# MOS_Switch.net
KiCad netlist of a schematic drawn in Altium Designer
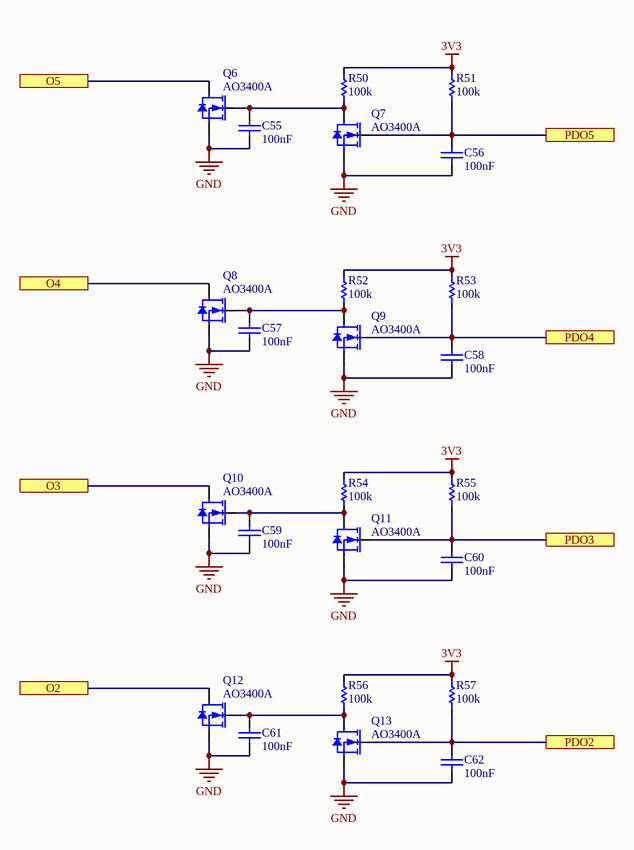
[diagram p0: MOS Switch.SchDoc]

(export (version "E")
  (design (tool "Eeschema 10.0.6"))
  (components
    (comp (ref "C55")
      (value "100nF")
      (footprint "CAP_CHIP_0603")
      (description "0603 Multilayer Ceramic Capacitors MLCC")
      (fields (field (name "PARTNUMBER") "CC0603KRX7R9BB104") (field (name "TOLERANCE") "10%"))
      (libsource (lib "Sainsbury Wellcome Centre") (part "Cap"))
    )
    (comp (ref "C56")
      (value "100nF")
      (footprint "CAP_CHIP_0603")
      (description "0603 Multilayer Ceramic Capacitors MLCC")
      (fields (field (name "PARTNUMBER") "CC0603KRX7R9BB104") (field (name "TOLERANCE") "10%"))
      (libsource (lib "Sainsbury Wellcome Centre") (part "Cap"))
    )
    (comp (ref "C57")
      (value "100nF")
      (footprint "CAP_CHIP_0603")
      (description "0603 Multilayer Ceramic Capacitors MLCC")
      (fields (field (name "PARTNUMBER") "CC0603KRX7R9BB104") (field (name "TOLERANCE") "10%"))
      (libsource (lib "Sainsbury Wellcome Centre") (part "Cap"))
    )
    (comp (ref "C58")
      (value "100nF")
      (footprint "CAP_CHIP_0603")
      (description "0603 Multilayer Ceramic Capacitors MLCC")
      (fields (field (name "PARTNUMBER") "CC0603KRX7R9BB104") (field (name "TOLERANCE") "10%"))
      (libsource (lib "Sainsbury Wellcome Centre") (part "Cap"))
    )
    (comp (ref "C59")
      (value "100nF")
      (footprint "CAP_CHIP_0603")
      (description "0603 Multilayer Ceramic Capacitors MLCC")
      (fields (field (name "PARTNUMBER") "CC0603KRX7R9BB104") (field (name "TOLERANCE") "10%"))
      (libsource (lib "Sainsbury Wellcome Centre") (part "Cap"))
    )
    (comp (ref "C60")
      (value "100nF")
      (footprint "CAP_CHIP_0603")
      (description "0603 Multilayer Ceramic Capacitors MLCC")
      (fields (field (name "PARTNUMBER") "CC0603KRX7R9BB104") (field (name "TOLERANCE") "10%"))
      (libsource (lib "Sainsbury Wellcome Centre") (part "Cap"))
    )
    (comp (ref "C61")
      (value "100nF")
      (footprint "CAP_CHIP_0603")
      (description "0603 Multilayer Ceramic Capacitors MLCC")
      (fields (field (name "PARTNUMBER") "CC0603KRX7R9BB104") (field (name "TOLERANCE") "10%"))
      (libsource (lib "Sainsbury Wellcome Centre") (part "Cap"))
    )
    (comp (ref "C62")
      (value "100nF")
      (footprint "CAP_CHIP_0603")
      (description "0603 Multilayer Ceramic Capacitors MLCC")
      (fields (field (name "PARTNUMBER") "CC0603KRX7R9BB104") (field (name "TOLERANCE") "10%"))
      (libsource (lib "Sainsbury Wellcome Centre") (part "Cap"))
    )
    (comp (ref "Q6")
      (value "AO3400A")
      (footprint "SOT23")
      (description "30V 5.7A 26.5mΩ@10V,5.7A 1.4W 1.5V@250uA 1 NChannel SOT-23-3L MOSFETs")
      (fields (field (name "PARTNUMBER") "AO3400A"))
      (libsource (lib "Sainsbury Wellcome Centre") (part "NMOS"))
    )
    (comp (ref "Q7")
      (value "AO3400A")
      (footprint "SOT23")
      (description "30V 5.7A 26.5mΩ@10V,5.7A 1.4W 1.5V@250uA 1 NChannel SOT-23-3L MOSFETs")
      (fields (field (name "PARTNUMBER") "AO3400A"))
      (libsource (lib "Sainsbury Wellcome Centre") (part "NMOS"))
    )
    (comp (ref "Q8")
      (value "AO3400A")
      (footprint "SOT23")
      (description "30V 5.7A 26.5mΩ@10V,5.7A 1.4W 1.5V@250uA 1 NChannel SOT-23-3L MOSFETs")
      (fields (field (name "PARTNUMBER") "AO3400A"))
      (libsource (lib "Sainsbury Wellcome Centre") (part "NMOS"))
    )
    (comp (ref "Q9")
      (value "AO3400A")
      (footprint "SOT23")
      (description "30V 5.7A 26.5mΩ@10V,5.7A 1.4W 1.5V@250uA 1 NChannel SOT-23-3L MOSFETs")
      (fields (field (name "PARTNUMBER") "AO3400A"))
      (libsource (lib "Sainsbury Wellcome Centre") (part "NMOS"))
    )
    (comp (ref "Q10")
      (value "AO3400A")
      (footprint "SOT23")
      (description "30V 5.7A 26.5mΩ@10V,5.7A 1.4W 1.5V@250uA 1 NChannel SOT-23-3L MOSFETs")
      (fields (field (name "PARTNUMBER") "AO3400A"))
      (libsource (lib "Sainsbury Wellcome Centre") (part "NMOS"))
    )
    (comp (ref "Q11")
      (value "AO3400A")
      (footprint "SOT23")
      (description "30V 5.7A 26.5mΩ@10V,5.7A 1.4W 1.5V@250uA 1 NChannel SOT-23-3L MOSFETs")
      (fields (field (name "PARTNUMBER") "AO3400A"))
      (libsource (lib "Sainsbury Wellcome Centre") (part "NMOS"))
    )
    (comp (ref "Q12")
      (value "AO3400A")
      (footprint "SOT23")
      (description "30V 5.7A 26.5mΩ@10V,5.7A 1.4W 1.5V@250uA 1 NChannel SOT-23-3L MOSFETs")
      (fields (field (name "PARTNUMBER") "AO3400A"))
      (libsource (lib "Sainsbury Wellcome Centre") (part "NMOS"))
    )
    (comp (ref "Q13")
      (value "AO3400A")
      (footprint "SOT23")
      (description "30V 5.7A 26.5mΩ@10V,5.7A 1.4W 1.5V@250uA 1 NChannel SOT-23-3L MOSFETs")
      (fields (field (name "PARTNUMBER") "AO3400A"))
      (libsource (lib "Sainsbury Wellcome Centre") (part "NMOS"))
    )
    (comp (ref "R50")
      (value "100k")
      (footprint "RES_CHIP_0603")
      (description "100mW Thick Film Resistors 75V ±100ppm/℃ ±1% 0603 Chip Resistor")
      (fields (field (name "PARTNUMBER") "0603WAF1003T5E") (field (name "TOLERANCE") "1%"))
      (libsource (lib "Sainsbury Wellcome Centre") (part "Res"))
    )
    (comp (ref "R51")
      (value "100k")
      (footprint "RES_CHIP_0603")
      (description "100mW Thick Film Resistors 75V ±100ppm/℃ ±1% 0603 Chip Resistor")
      (fields (field (name "PARTNUMBER") "0603WAF1003T5E") (field (name "TOLERANCE") "1%"))
      (libsource (lib "Sainsbury Wellcome Centre") (part "Res"))
    )
    (comp (ref "R52")
      (value "100k")
      (footprint "RES_CHIP_0603")
      (description "100mW Thick Film Resistors 75V ±100ppm/℃ ±1% 0603 Chip Resistor")
      (fields (field (name "PARTNUMBER") "0603WAF1003T5E") (field (name "TOLERANCE") "1%"))
      (libsource (lib "Sainsbury Wellcome Centre") (part "Res"))
    )
    (comp (ref "R53")
      (value "100k")
      (footprint "RES_CHIP_0603")
      (description "100mW Thick Film Resistors 75V ±100ppm/℃ ±1% 0603 Chip Resistor")
      (fields (field (name "PARTNUMBER") "0603WAF1003T5E") (field (name "TOLERANCE") "1%"))
      (libsource (lib "Sainsbury Wellcome Centre") (part "Res"))
    )
    (comp (ref "R54")
      (value "100k")
      (footprint "RES_CHIP_0603")
      (description "100mW Thick Film Resistors 75V ±100ppm/℃ ±1% 0603 Chip Resistor")
      (fields (field (name "PARTNUMBER") "0603WAF1003T5E") (field (name "TOLERANCE") "1%"))
      (libsource (lib "Sainsbury Wellcome Centre") (part "Res"))
    )
    (comp (ref "R55")
      (value "100k")
      (footprint "RES_CHIP_0603")
      (description "100mW Thick Film Resistors 75V ±100ppm/℃ ±1% 0603 Chip Resistor")
      (fields (field (name "PARTNUMBER") "0603WAF1003T5E") (field (name "TOLERANCE") "1%"))
      (libsource (lib "Sainsbury Wellcome Centre") (part "Res"))
    )
    (comp (ref "R56")
      (value "100k")
      (footprint "RES_CHIP_0603")
      (description "100mW Thick Film Resistors 75V ±100ppm/℃ ±1% 0603 Chip Resistor")
      (fields (field (name "PARTNUMBER") "0603WAF1003T5E") (field (name "TOLERANCE") "1%"))
      (libsource (lib "Sainsbury Wellcome Centre") (part "Res"))
    )
    (comp (ref "R57")
      (value "100k")
      (footprint "RES_CHIP_0603")
      (description "100mW Thick Film Resistors 75V ±100ppm/℃ ±1% 0603 Chip Resistor")
      (fields (field (name "PARTNUMBER") "0603WAF1003T5E") (field (name "TOLERANCE") "1%"))
      (libsource (lib "Sainsbury Wellcome Centre") (part "Res"))
    )
  )
  (nets
    (net (code "1") (name "/O2") (class "Default")
      (node (ref "Q12") (pin "3") (pinfunction "D_3") (pintype "passive"))
    )
    (net (code "2") (name "/O3") (class "Default")
      (node (ref "Q10") (pin "3") (pinfunction "D_3") (pintype "passive"))
    )
    (net (code "3") (name "/O4") (class "Default")
      (node (ref "Q8") (pin "3") (pinfunction "D_3") (pintype "passive"))
    )
    (net (code "4") (name "/O5") (class "Default")
      (node (ref "Q6") (pin "3") (pinfunction "D_3") (pintype "passive"))
    )
    (net (code "5") (name "/PDO2") (class "Default")
      (node (ref "C62") (pin "2") (pinfunction "2_2") (pintype "passive"))
      (node (ref "Q13") (pin "1") (pinfunction "G_1") (pintype "passive"))
      (node (ref "R57") (pin "1") (pinfunction "1_1") (pintype "passive"))
    )
    (net (code "6") (name "/PDO3") (class "Default")
      (node (ref "C60") (pin "2") (pinfunction "2_2") (pintype "passive"))
      (node (ref "Q11") (pin "1") (pinfunction "G_1") (pintype "passive"))
      (node (ref "R55") (pin "1") (pinfunction "1_1") (pintype "passive"))
    )
    (net (code "7") (name "/PDO4") (class "Default")
      (node (ref "C58") (pin "2") (pinfunction "2_2") (pintype "passive"))
      (node (ref "Q9") (pin "1") (pinfunction "G_1") (pintype "passive"))
      (node (ref "R53") (pin "1") (pinfunction "1_1") (pintype "passive"))
    )
    (net (code "8") (name "/PDO5") (class "Default")
      (node (ref "C56") (pin "2") (pinfunction "2_2") (pintype "passive"))
      (node (ref "Q7") (pin "1") (pinfunction "G_1") (pintype "passive"))
      (node (ref "R51") (pin "1") (pinfunction "1_1") (pintype "passive"))
    )
    (net (code "9") (name "3V3") (class "Default")
      (node (ref "R50") (pin "2") (pinfunction "2_2") (pintype "passive"))
      (node (ref "R51") (pin "2") (pinfunction "2_2") (pintype "passive"))
      (node (ref "R52") (pin "2") (pinfunction "2_2") (pintype "passive"))
      (node (ref "R53") (pin "2") (pinfunction "2_2") (pintype "passive"))
      (node (ref "R54") (pin "2") (pinfunction "2_2") (pintype "passive"))
      (node (ref "R55") (pin "2") (pinfunction "2_2") (pintype "passive"))
      (node (ref "R56") (pin "2") (pinfunction "2_2") (pintype "passive"))
      (node (ref "R57") (pin "2") (pinfunction "2_2") (pintype "passive"))
    )
    (net (code "10") (name "GND") (class "Default")
      (node (ref "C55") (pin "1") (pinfunction "1_1") (pintype "passive"))
      (node (ref "C56") (pin "1") (pinfunction "1_1") (pintype "passive"))
      (node (ref "C57") (pin "1") (pinfunction "1_1") (pintype "passive"))
      (node (ref "C58") (pin "1") (pinfunction "1_1") (pintype "passive"))
      (node (ref "C59") (pin "1") (pinfunction "1_1") (pintype "passive"))
      (node (ref "C60") (pin "1") (pinfunction "1_1") (pintype "passive"))
      (node (ref "C61") (pin "1") (pinfunction "1_1") (pintype "passive"))
      (node (ref "C62") (pin "1") (pinfunction "1_1") (pintype "passive"))
      (node (ref "Q10") (pin "2") (pinfunction "S_2") (pintype "passive"))
      (node (ref "Q11") (pin "2") (pinfunction "S_2") (pintype "passive"))
      (node (ref "Q12") (pin "2") (pinfunction "S_2") (pintype "passive"))
      (node (ref "Q13") (pin "2") (pinfunction "S_2") (pintype "passive"))
      (node (ref "Q6") (pin "2") (pinfunction "S_2") (pintype "passive"))
      (node (ref "Q7") (pin "2") (pinfunction "S_2") (pintype "passive"))
      (node (ref "Q8") (pin "2") (pinfunction "S_2") (pintype "passive"))
      (node (ref "Q9") (pin "2") (pinfunction "S_2") (pintype "passive"))
    )
    (net (code "11") (name "Net-(Q6-G)") (class "Default")
      (node (ref "C55") (pin "2") (pinfunction "2_2") (pintype "passive"))
      (node (ref "Q6") (pin "1") (pinfunction "G_1") (pintype "passive"))
      (node (ref "Q7") (pin "3") (pinfunction "D_3") (pintype "passive"))
      (node (ref "R50") (pin "1") (pinfunction "1_1") (pintype "passive"))
    )
    (net (code "12") (name "Net-(Q8-G)") (class "Default")
      (node (ref "C57") (pin "2") (pinfunction "2_2") (pintype "passive"))
      (node (ref "Q8") (pin "1") (pinfunction "G_1") (pintype "passive"))
      (node (ref "Q9") (pin "3") (pinfunction "D_3") (pintype "passive"))
      (node (ref "R52") (pin "1") (pinfunction "1_1") (pintype "passive"))
    )
    (net (code "13") (name "Net-(Q10-G)") (class "Default")
      (node (ref "C59") (pin "2") (pinfunction "2_2") (pintype "passive"))
      (node (ref "Q10") (pin "1") (pinfunction "G_1") (pintype "passive"))
      (node (ref "Q11") (pin "3") (pinfunction "D_3") (pintype "passive"))
      (node (ref "R54") (pin "1") (pinfunction "1_1") (pintype "passive"))
    )
    (net (code "14") (name "Net-(Q12-G)") (class "Default")
      (node (ref "C61") (pin "2") (pinfunction "2_2") (pintype "passive"))
      (node (ref "Q12") (pin "1") (pinfunction "G_1") (pintype "passive"))
      (node (ref "Q13") (pin "3") (pinfunction "D_3") (pintype "passive"))
      (node (ref "R56") (pin "1") (pinfunction "1_1") (pintype "passive"))
    )
  )
)
